# 2_MCU_schdoc.net
KiCad netlist of a schematic drawn in Altium Designer
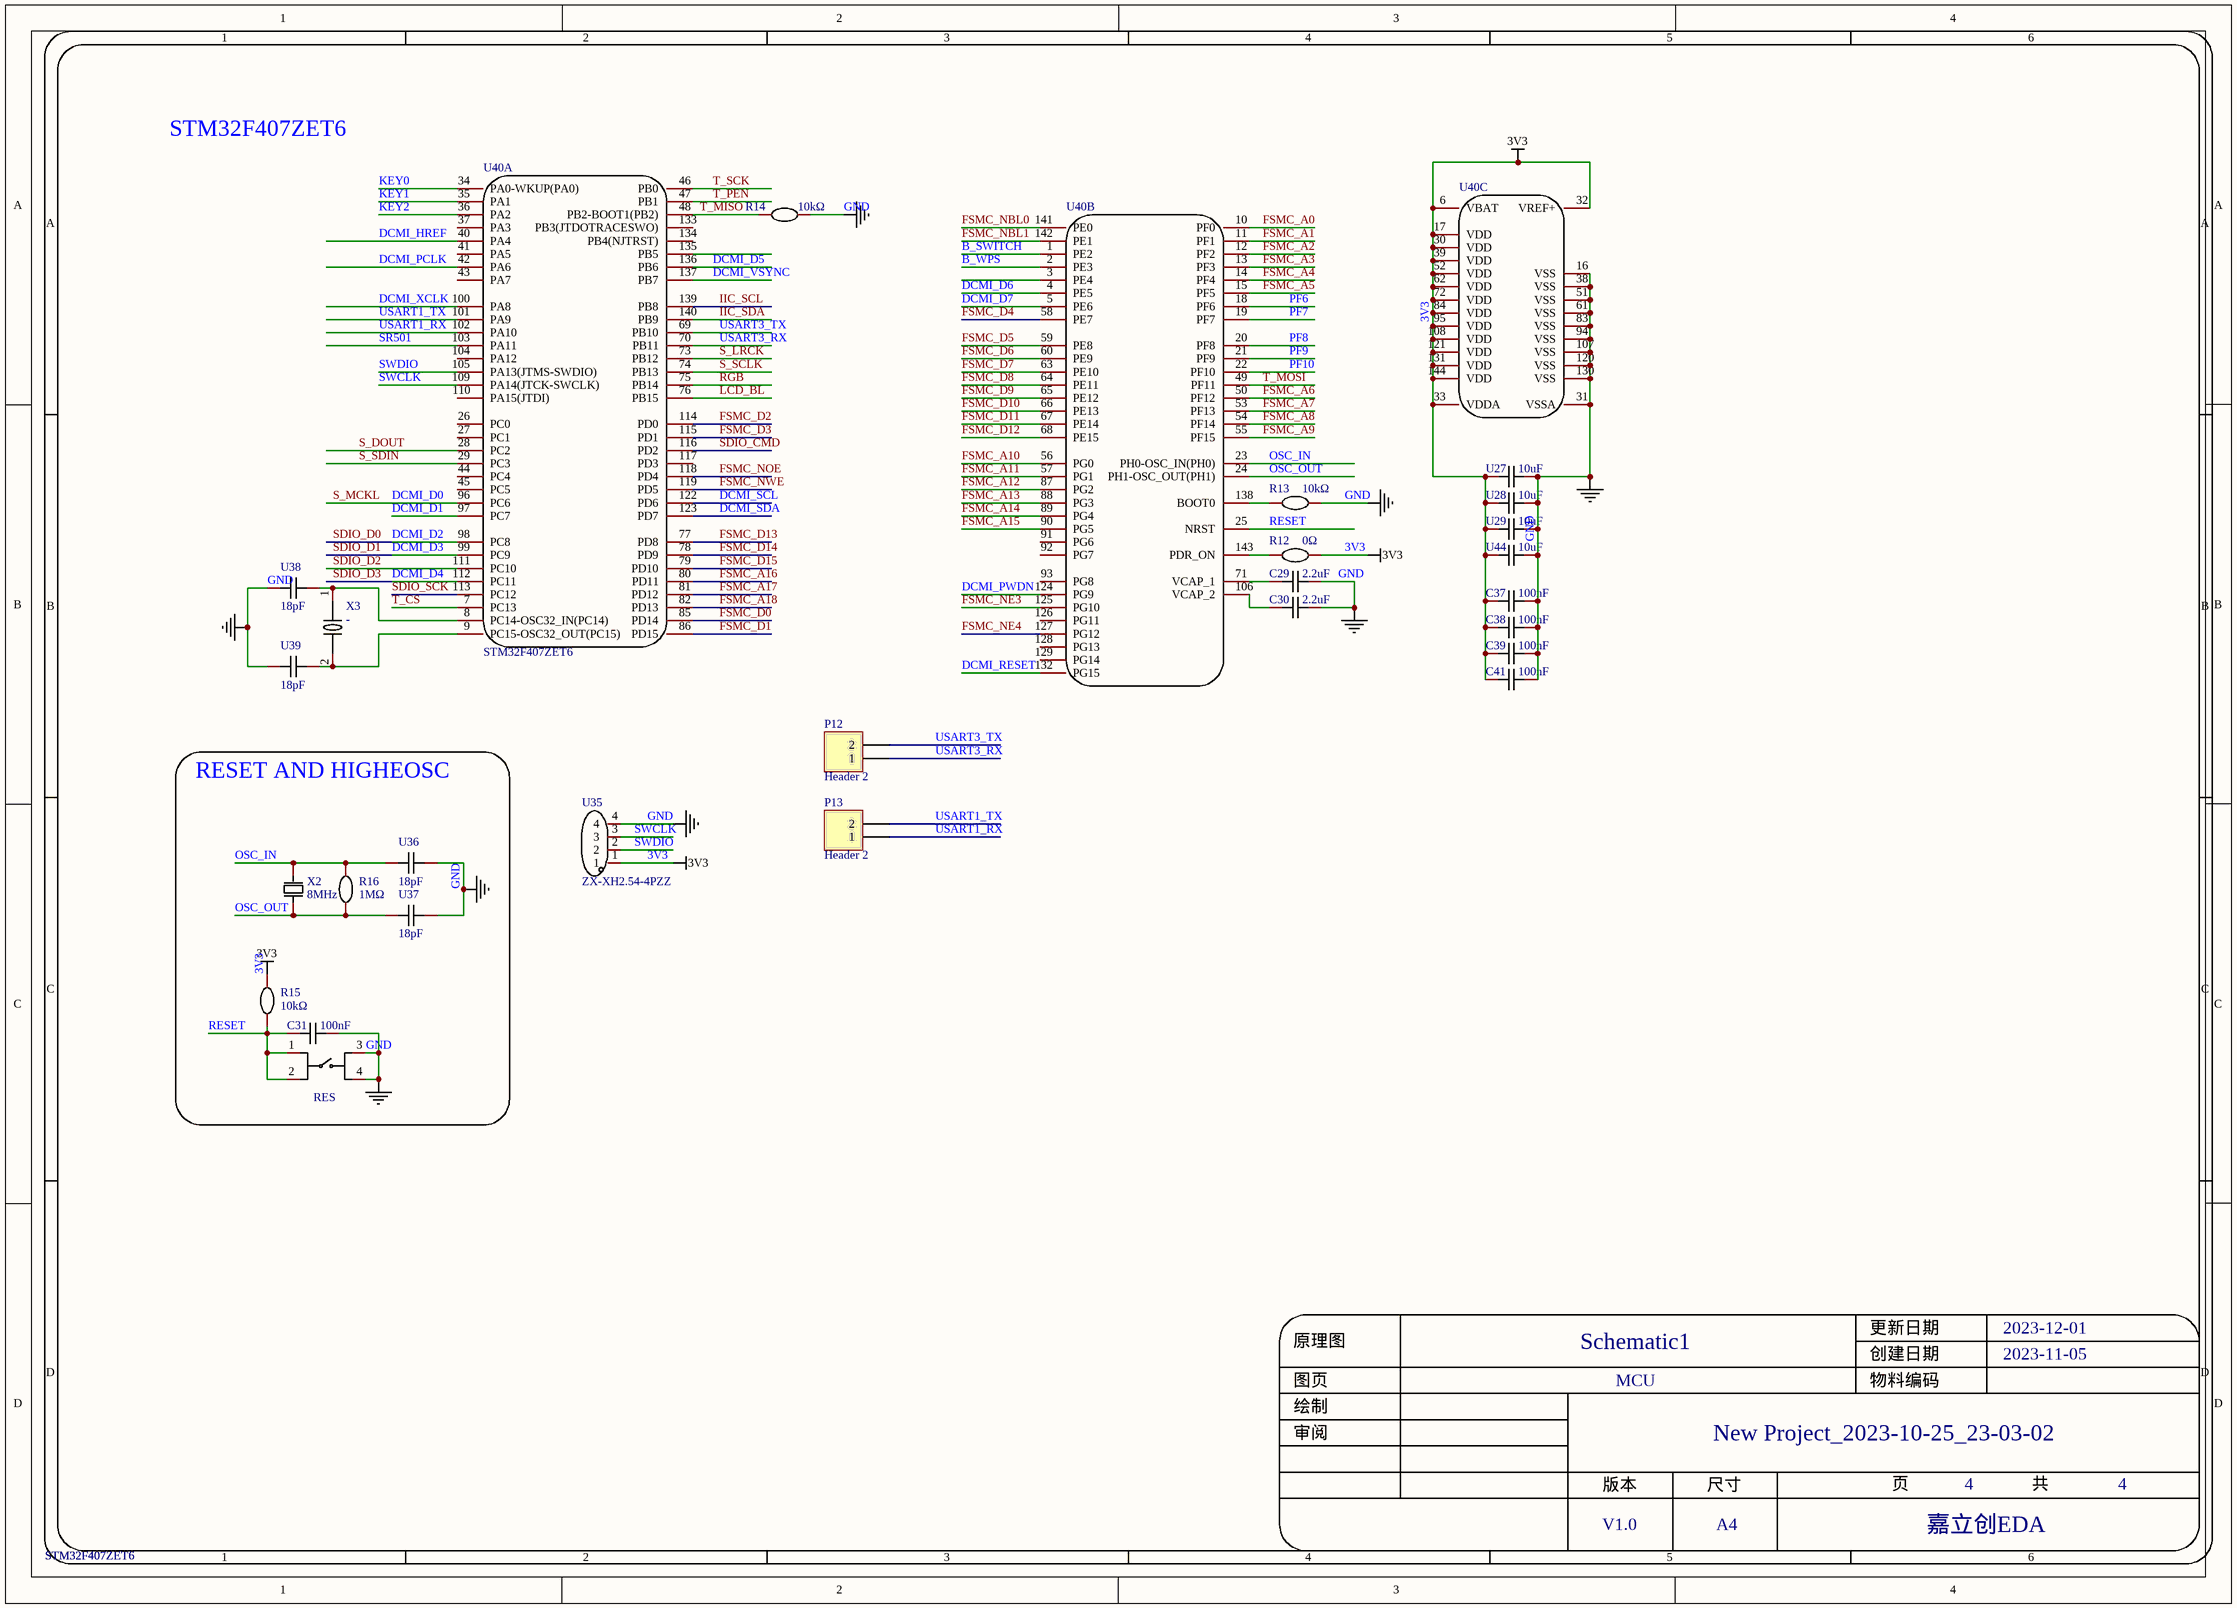
[diagram p0: 2_MCU.schdoc.schdoc]

(export (version "E")
  (design (tool "Eeschema 10.0.6"))
  (components
    (comp (ref "C29")
      (value "2.2uF")
      (footprint "C0603")
      (description "容值:2.2uF;精度:±10%;额定电压:10V;材质(温度系数):X6S;")
      (fields
        (field (name "NAME") "2.2uF")
        (field (name "MANUFACTURER") "TDK")
        (field (name "MANUFACTURER PART") "C1608X6S1A225K080AB")
      )
      (libsource (lib "altium-import") (part "root_0_C1608X6S1A225K080AB_"))
    )
    (comp (ref "C30")
      (value "2.2uF")
      (footprint "C0603")
      (description "容值:2.2uF;精度:±10%;额定电压:10V;材质(温度系数):X6S;")
      (fields
        (field (name "NAME") "2.2uF")
        (field (name "MANUFACTURER") "TDK")
        (field (name "MANUFACTURER PART") "C1608X6S1A225K080AB")
      )
      (libsource (lib "altium-import") (part "root_0_C1608X6S1A225K080AB_"))
    )
    (comp (ref "C31")
      (value "100nF")
      (footprint "C0603")
      (description "容值:100nF;精度:±20%;额定电压:50V;材质(温度系数):X8R;")
      (fields
        (field (name "NAME") "100nF")
        (field (name "MANUFACTURER") "TDK")
        (field (name "MANUFACTURER PART") "CGA3E3X8R1H104M080AE")
      )
      (libsource (lib "altium-import") (part "root_0_CGA3E3X8R1H104M080AE_"))
    )
    (comp (ref "C37")
      (value "100nF")
      (footprint "C0603")
      (description "容值:100nF;精度:±20%;额定电压:50V;材质(温度系数):X8R;")
      (fields
        (field (name "NAME") "100nF")
        (field (name "MANUFACTURER") "TDK")
        (field (name "MANUFACTURER PART") "CGA3E3X8R1H104M080AE")
      )
      (libsource (lib "altium-import") (part "root_0_CGA3E3X8R1H104M080AE_"))
    )
    (comp (ref "C38")
      (value "100nF")
      (footprint "C0603")
      (description "容值:100nF;精度:±20%;额定电压:50V;材质(温度系数):X8R;")
      (fields
        (field (name "NAME") "100nF")
        (field (name "MANUFACTURER") "TDK")
        (field (name "MANUFACTURER PART") "CGA3E3X8R1H104M080AE")
      )
      (libsource (lib "altium-import") (part "root_0_CGA3E3X8R1H104M080AE_"))
    )
    (comp (ref "C39")
      (value "100nF")
      (footprint "C0603")
      (description "容值:100nF;精度:±20%;额定电压:50V;材质(温度系数):X8R;")
      (fields
        (field (name "NAME") "100nF")
        (field (name "MANUFACTURER") "TDK")
        (field (name "MANUFACTURER PART") "CGA3E3X8R1H104M080AE")
      )
      (libsource (lib "altium-import") (part "root_0_CGA3E3X8R1H104M080AE_"))
    )
    (comp (ref "C41")
      (value "100nF")
      (footprint "C0603")
      (description "容值:100nF;精度:±20%;额定电压:50V;材质(温度系数):X8R;")
      (fields
        (field (name "NAME") "100nF")
        (field (name "MANUFACTURER") "TDK")
        (field (name "MANUFACTURER PART") "CGA3E3X8R1H104M080AE")
      )
      (libsource (lib "altium-import") (part "root_0_CGA3E3X8R1H104M080AE_"))
    )
    (comp (ref "P12")
      (value "Header 2")
      (footprint "HDR1X2")
      (description "Header, 2-Pin")
      (fields (field (name "PUBLISHER") "Altium Limited"))
      (libsource (lib "Miscellaneous Connectors") (part "Header 2"))
    )
    (comp (ref "P13")
      (value "Header 2")
      (footprint "HDR1X2")
      (description "Header, 2-Pin")
      (fields (field (name "PUBLISHER") "Altium Limited"))
      (libsource (lib "Miscellaneous Connectors") (part "Header 2"))
    )
    (comp (ref "R12")
      (value "0Ω")
      (footprint "R0603")
      (description "电阻类型:厚膜电阻;阻值:0Ω;精度:-;功率:100mW;")
      (fields
        (field (name "NAME") "0Ω")
        (field (name "MANUFACTURER") "YAGEO(国巨)")
        (field (name "MANUFACTURER PART") "RC0603JR-130RL")
      )
      (libsource (lib "altium-import") (part "root_0_RC0603JR-130RL_"))
    )
    (comp (ref "R13")
      (value "10kΩ")
      (footprint "R0603")
      (description "阻值:10kΩ;精度:±5%;")
      (fields
        (field (name "NAME") "10kΩ")
        (field (name "MANUFACTURER") "VO(翔胜)")
        (field (name "MANUFACTURER PART") "SCR0603J10K")
      )
      (libsource (lib "altium-import") (part "root_0_SCR0603J10K_"))
    )
    (comp (ref "R14")
      (value "10kΩ")
      (footprint "R0603")
      (description "阻值:10kΩ;精度:±5%;")
      (fields
        (field (name "NAME") "10kΩ")
        (field (name "MANUFACTURER") "VO(翔胜)")
        (field (name "MANUFACTURER PART") "SCR0603J10K")
      )
      (libsource (lib "altium-import") (part "root_0_SCR0603J10K_"))
    )
    (comp (ref "R15")
      (value "10kΩ")
      (footprint "R0603")
      (description "阻值:10kΩ;精度:±5%;")
      (fields
        (field (name "NAME") "10kΩ")
        (field (name "MANUFACTURER") "VO(翔胜)")
        (field (name "MANUFACTURER PART") "SCR0603J10K")
      )
      (libsource (lib "altium-import") (part "root_1_SCR0603J10K_"))
    )
    (comp (ref "R16")
      (value "1MΩ")
      (footprint "R0603")
      (description "电阻类型:厚膜电阻;阻值:1MΩ;精度:±5%;功率:100mW;")
      (fields
        (field (name "NAME") "1MΩ")
        (field (name "MANUFACTURER") "VISHAY(威世)")
        (field (name "MANUFACTURER PART") "CRCW06031M00JNEAC")
      )
      (libsource (lib "altium-import") (part "root_1_CRCW06031M00JNEAC_"))
    )
    (comp (ref "RES")
      (value "K2-6639SP-C4SC-04")
      (footprint "KEY-SMD_4P-L6.0-W6.0-P3.90-LS10.0")
      (fields (field (name "MANUFACTURER") "韩国韩荣"))
      (libsource (lib "altium-import") (part "root_0_K2-6639SP-C4SC-04_"))
    )
    (comp (ref "U27")
      (value "10uF")
      (footprint "C0603")
      (description "容值:10uF;精度:±20%;额定电压:16V;材质(温度系数):JB;")
      (fields
        (field (name "NAME") "10uF")
        (field (name "MANUFACTURER") "TDK")
        (field (name "MANUFACTURER PART") "C1608JB1C106M080AB")
      )
      (libsource (lib "altium-import") (part "root_0_C1608JB1C106M080AB_"))
    )
    (comp (ref "U28")
      (value "10uF")
      (footprint "C0603")
      (description "容值:10uF;精度:±20%;额定电压:16V;材质(温度系数):JB;")
      (fields
        (field (name "NAME") "10uF")
        (field (name "MANUFACTURER") "TDK")
        (field (name "MANUFACTURER PART") "C1608JB1C106M080AB")
      )
      (libsource (lib "altium-import") (part "root_0_C1608JB1C106M080AB_"))
    )
    (comp (ref "U29")
      (value "10uF")
      (footprint "C0603")
      (description "容值:10uF;精度:±20%;额定电压:16V;材质(温度系数):JB;")
      (fields
        (field (name "NAME") "10uF")
        (field (name "MANUFACTURER") "TDK")
        (field (name "MANUFACTURER PART") "C1608JB1C106M080AB")
      )
      (libsource (lib "altium-import") (part "root_0_C1608JB1C106M080AB_"))
    )
    (comp (ref "U35")
      (value "ZX-XH2.54-4PZZ")
      (footprint "CONN-TH_4P-P2.50_4PIN")
      (fields (field (name "NAME") "ZX-XH2.54-4PZZ") (field (name "MANUFACTURER") "Megastar(兆星)"))
      (libsource (lib "altium-import") (part "root_2_ZX-XH2.54-4PZZ_"))
    )
    (comp (ref "U36")
      (value "18pF")
      (footprint "C0603")
      (description "容值:18pF;精度:±5%;额定电压:100V;材质(温度系数):CH;")
      (fields
        (field (name "NAME") "18pF")
        (field (name "MANUFACTURER") "TDK")
        (field (name "MANUFACTURER PART") "C1608CH2A180J080AA")
      )
      (libsource (lib "altium-import") (part "root_0_C1608CH2A180J080AA_"))
    )
    (comp (ref "U37")
      (value "18pF")
      (footprint "C0603")
      (description "容值:18pF;精度:±5%;额定电压:100V;材质(温度系数):CH;")
      (fields
        (field (name "NAME") "18pF")
        (field (name "MANUFACTURER") "TDK")
        (field (name "MANUFACTURER PART") "C1608CH2A180J080AA")
      )
      (libsource (lib "altium-import") (part "root_0_C1608CH2A180J080AA_"))
    )
    (comp (ref "U38")
      (value "18pF")
      (footprint "C0603")
      (description "容值:18pF;精度:±5%;额定电压:100V;材质(温度系数):CH;")
      (fields
        (field (name "NAME") "18pF")
        (field (name "MANUFACTURER") "TDK")
        (field (name "MANUFACTURER PART") "C1608CH2A180J080AA")
      )
      (libsource (lib "altium-import") (part "root_0_C1608CH2A180J080AA_"))
    )
    (comp (ref "U39")
      (value "18pF")
      (footprint "C0603")
      (description "容值:18pF;精度:±5%;额定电压:100V;材质(温度系数):CH;")
      (fields
        (field (name "NAME") "18pF")
        (field (name "MANUFACTURER") "TDK")
        (field (name "MANUFACTURER PART") "C1608CH2A180J080AA")
      )
      (libsource (lib "altium-import") (part "root_0_C1608CH2A180J080AA_"))
    )
    (comp (ref "U40")
      (value "STM32F407ZET6")
      (footprint "LQFP-144_L20.0-W20.0-P0.50-LS22.0-BL")
      (fields (field (name "NAME") "STM32F407ZET6") (field (name "MANUFACTURER") "ST(意法半导体)"))
      (libsource (lib "altium-import") (part "root_0_STM32F407ZET6_"))
    )
    (comp (ref "U44")
      (value "10uF")
      (footprint "C0603")
      (description "容值:10uF;精度:±20%;额定电压:16V;材质(温度系数):JB;")
      (fields
        (field (name "NAME") "10uF")
        (field (name "MANUFACTURER") "TDK")
        (field (name "MANUFACTURER PART") "C1608JB1C106M080AB")
      )
      (libsource (lib "altium-import") (part "root_0_C1608JB1C106M080AB_"))
    )
    (comp (ref "X2")
      (value "8MHz")
      (footprint "OSC-SMD_L5.0-W3.2")
      (description "频率:8MHz;频率公差:±30ppm;负载电容:20pF;")
      (fields
        (field (name "NAME") "8MHz")
        (field (name "MANUFACTURER") "TAE(雅晶鑫)")
        (field (name "MANUFACTURER PART") "TAXM8M2QLFCDT1T")
      )
      (libsource (lib "altium-import") (part "root_1_TAXM8M2QLFCDT1T_"))
    )
    (comp (ref "X3")
      (value "-")
      (footprint "OSC-SMD_2P-L1.6-W1.0")
      (description "频率:-;负载电容:-;")
      (fields
        (field (name "NAME") "-")
        (field (name "MANUFACTURER") "RIVER(大河)")
        (field (name "MANUFACTURER PART") "TFX-04-32.768K")
      )
      (libsource (lib "altium-import") (part "root_3_TFX-04-32.768K_"))
    )
  )
  (nets
    (net (code "1") (name "/B_SWITCH") (class "Default")
      (node (ref "U40") (pin "1") (pinfunction "PE2_1") (pintype "passive"))
    )
    (net (code "2") (name "/B_WPS") (class "Default")
      (node (ref "U40") (pin "2") (pinfunction "PE3_2") (pintype "passive"))
    )
    (net (code "3") (name "/DCMI_D0") (class "Default")
      (node (ref "U40") (pin "96") (pinfunction "PC6_96") (pintype "passive"))
    )
    (net (code "4") (name "/DCMI_D1") (class "Default")
      (node (ref "U40") (pin "97") (pinfunction "PC7_97") (pintype "passive"))
    )
    (net (code "5") (name "/DCMI_D2") (class "Default")
      (node (ref "U40") (pin "98") (pinfunction "PC8_98") (pintype "passive"))
    )
    (net (code "6") (name "/DCMI_D3") (class "Default")
      (node (ref "U40") (pin "99") (pinfunction "PC9_99") (pintype "passive"))
    )
    (net (code "7") (name "/DCMI_D4") (class "Default")
      (node (ref "U40") (pin "112") (pinfunction "PC11_112") (pintype "passive"))
    )
    (net (code "8") (name "/DCMI_D5") (class "Default")
      (node (ref "U40") (pin "136") (pinfunction "PB6_136") (pintype "passive"))
    )
    (net (code "9") (name "/DCMI_D6") (class "Default")
      (node (ref "U40") (pin "4") (pinfunction "PE5_4") (pintype "passive"))
    )
    (net (code "10") (name "/DCMI_D7") (class "Default")
      (node (ref "U40") (pin "5") (pinfunction "PE6_5") (pintype "passive"))
    )
    (net (code "11") (name "/DCMI_HREF") (class "Default")
      (node (ref "U40") (pin "40") (pinfunction "PA4_40") (pintype "passive"))
    )
    (net (code "12") (name "/DCMI_PCLK") (class "Default")
      (node (ref "U40") (pin "42") (pinfunction "PA6_42") (pintype "passive"))
    )
    (net (code "13") (name "/DCMI_PWDN") (class "Default")
      (node (ref "U40") (pin "124") (pinfunction "PG9_124") (pintype "passive"))
    )
    (net (code "14") (name "/DCMI_RESET") (class "Default")
      (node (ref "U40") (pin "132") (pinfunction "PG15_132") (pintype "passive"))
    )
    (net (code "15") (name "/DCMI_SCL") (class "Default")
      (node (ref "U40") (pin "122") (pinfunction "PD6_122") (pintype "passive"))
    )
    (net (code "16") (name "/DCMI_SDA") (class "Default")
      (node (ref "U40") (pin "123") (pinfunction "PD7_123") (pintype "passive"))
    )
    (net (code "17") (name "/DCMI_VSYNC") (class "Default")
      (node (ref "U40") (pin "137") (pinfunction "PB7_137") (pintype "passive"))
    )
    (net (code "18") (name "/DCMI_XCLK") (class "Default")
      (node (ref "U40") (pin "100") (pinfunction "PA8_100") (pintype "passive"))
    )
    (net (code "19") (name "/FSMC_A0") (class "Default")
      (node (ref "U40") (pin "10") (pinfunction "PF0_10") (pintype "passive"))
    )
    (net (code "20") (name "/FSMC_A1") (class "Default")
      (node (ref "U40") (pin "11") (pinfunction "PF1_11") (pintype "passive"))
    )
    (net (code "21") (name "/FSMC_A2") (class "Default")
      (node (ref "U40") (pin "12") (pinfunction "PF2_12") (pintype "passive"))
    )
    (net (code "22") (name "/FSMC_A3") (class "Default")
      (node (ref "U40") (pin "13") (pinfunction "PF3_13") (pintype "passive"))
    )
    (net (code "23") (name "/FSMC_A4") (class "Default")
      (node (ref "U40") (pin "14") (pinfunction "PF4_14") (pintype "passive"))
    )
    (net (code "24") (name "/FSMC_A5") (class "Default")
      (node (ref "U40") (pin "15") (pinfunction "PF5_15") (pintype "passive"))
    )
    (net (code "25") (name "/FSMC_A6") (class "Default")
      (node (ref "U40") (pin "50") (pinfunction "PF12_50") (pintype "passive"))
    )
    (net (code "26") (name "/FSMC_A7") (class "Default")
      (node (ref "U40") (pin "53") (pinfunction "PF13_53") (pintype "passive"))
    )
    (net (code "27") (name "/FSMC_A8") (class "Default")
      (node (ref "U40") (pin "54") (pinfunction "PF14_54") (pintype "passive"))
    )
    (net (code "28") (name "/FSMC_A9") (class "Default")
      (node (ref "U40") (pin "55") (pinfunction "PF15_55") (pintype "passive"))
    )
    (net (code "29") (name "/FSMC_A10") (class "Default")
      (node (ref "U40") (pin "56") (pinfunction "PG0_56") (pintype "passive"))
    )
    (net (code "30") (name "/FSMC_A11") (class "Default")
      (node (ref "U40") (pin "57") (pinfunction "PG1_57") (pintype "passive"))
    )
    (net (code "31") (name "/FSMC_A12") (class "Default")
      (node (ref "U40") (pin "87") (pinfunction "PG2_87") (pintype "passive"))
    )
    (net (code "32") (name "/FSMC_A13") (class "Default")
      (node (ref "U40") (pin "88") (pinfunction "PG3_88") (pintype "passive"))
    )
    (net (code "33") (name "/FSMC_A14") (class "Default")
      (node (ref "U40") (pin "89") (pinfunction "PG4_89") (pintype "passive"))
    )
    (net (code "34") (name "/FSMC_A15") (class "Default")
      (node (ref "U40") (pin "90") (pinfunction "PG5_90") (pintype "passive"))
    )
    (net (code "35") (name "/FSMC_A16") (class "Default")
      (node (ref "U40") (pin "80") (pinfunction "PD11_80") (pintype "passive"))
    )
    (net (code "36") (name "/FSMC_A17") (class "Default")
      (node (ref "U40") (pin "81") (pinfunction "PD12_81") (pintype "passive"))
    )
    (net (code "37") (name "/FSMC_A18") (class "Default")
      (node (ref "U40") (pin "82") (pinfunction "PD13_82") (pintype "passive"))
    )
    (net (code "38") (name "/FSMC_D0") (class "Default")
      (node (ref "U40") (pin "85") (pinfunction "PD14_85") (pintype "passive"))
    )
    (net (code "39") (name "/FSMC_D1") (class "Default")
      (node (ref "U40") (pin "86") (pinfunction "PD15_86") (pintype "passive"))
    )
    (net (code "40") (name "/FSMC_D2") (class "Default")
      (node (ref "U40") (pin "114") (pinfunction "PD0_114") (pintype "passive"))
    )
    (net (code "41") (name "/FSMC_D3") (class "Default")
      (node (ref "U40") (pin "115") (pinfunction "PD1_115") (pintype "passive"))
    )
    (net (code "42") (name "/FSMC_D4") (class "Default")
      (node (ref "U40") (pin "58") (pinfunction "PE7_58") (pintype "passive"))
    )
    (net (code "43") (name "/FSMC_D5") (class "Default")
      (node (ref "U40") (pin "59") (pinfunction "PE8_59") (pintype "passive"))
    )
    (net (code "44") (name "/FSMC_D6") (class "Default")
      (node (ref "U40") (pin "60") (pinfunction "PE9_60") (pintype "passive"))
    )
    (net (code "45") (name "/FSMC_D7") (class "Default")
      (node (ref "U40") (pin "63") (pinfunction "PE10_63") (pintype "passive"))
    )
    (net (code "46") (name "/FSMC_D8") (class "Default")
      (node (ref "U40") (pin "64") (pinfunction "PE11_64") (pintype "passive"))
    )
    (net (code "47") (name "/FSMC_D9") (class "Default")
      (node (ref "U40") (pin "65") (pinfunction "PE12_65") (pintype "passive"))
    )
    (net (code "48") (name "/FSMC_D10") (class "Default")
      (node (ref "U40") (pin "66") (pinfunction "PE13_66") (pintype "passive"))
    )
    (net (code "49") (name "/FSMC_D11") (class "Default")
      (node (ref "U40") (pin "67") (pinfunction "PE14_67") (pintype "passive"))
    )
    (net (code "50") (name "/FSMC_D12") (class "Default")
      (node (ref "U40") (pin "68") (pinfunction "PE15_68") (pintype "passive"))
    )
    (net (code "51") (name "/FSMC_D13") (class "Default")
      (node (ref "U40") (pin "77") (pinfunction "PD8_77") (pintype "passive"))
    )
    (net (code "52") (name "/FSMC_D14") (class "Default")
      (node (ref "U40") (pin "78") (pinfunction "PD9_78") (pintype "passive"))
    )
    (net (code "53") (name "/FSMC_D15") (class "Default")
      (node (ref "U40") (pin "79") (pinfunction "PD10_79") (pintype "passive"))
    )
    (net (code "54") (name "/FSMC_NBL0") (class "Default")
      (node (ref "U40") (pin "141") (pinfunction "PE0_141") (pintype "passive"))
    )
    (net (code "55") (name "/FSMC_NBL1") (class "Default")
      (node (ref "U40") (pin "142") (pinfunction "PE1_142") (pintype "passive"))
    )
    (net (code "56") (name "/FSMC_NE3") (class "Default")
      (node (ref "U40") (pin "125") (pinfunction "PG10_125") (pintype "passive"))
    )
    (net (code "57") (name "/FSMC_NE4") (class "Default")
      (node (ref "U40") (pin "127") (pinfunction "PG12_127") (pintype "passive"))
    )
    (net (code "58") (name "/FSMC_NOE") (class "Default")
      (node (ref "U40") (pin "118") (pinfunction "PD4_118") (pintype "passive"))
    )
    (net (code "59") (name "/FSMC_NWE") (class "Default")
      (node (ref "U40") (pin "119") (pinfunction "PD5_119") (pintype "passive"))
    )
    (net (code "60") (name "/GND") (class "Default")
      (node (ref "C29") (pin "2") (pinfunction "2_2") (pintype "passive"))
      (node (ref "C30") (pin "2") (pinfunction "2_2") (pintype "passive"))
      (node (ref "C31") (pin "2") (pinfunction "2_2") (pintype "passive"))
      (node (ref "C37") (pin "2") (pinfunction "2_2") (pintype "passive"))
      (node (ref "C38") (pin "2") (pinfunction "2_2") (pintype "passive"))
      (node (ref "C39") (pin "2") (pinfunction "2_2") (pintype "passive"))
      (node (ref "C41") (pin "2") (pinfunction "2_2") (pintype "passive"))
      (node (ref "R13") (pin "2") (pinfunction "2_2") (pintype "passive"))
      (node (ref "R14") (pin "2") (pinfunction "2_2") (pintype "passive"))
      (node (ref "RES") (pin "3") (pinfunction "3_3") (pintype "passive"))
      (node (ref "RES") (pin "4") (pinfunction "4_4") (pintype "passive"))
      (node (ref "U27") (pin "2") (pinfunction "2_2") (pintype "passive"))
      (node (ref "U28") (pin "2") (pinfunction "2_2") (pintype "passive"))
      (node (ref "U29") (pin "2") (pinfunction "2_2") (pintype "passive"))
      (node (ref "U35") (pin "4") (pinfunction "4_4") (pintype "passive"))
      (node (ref "U36") (pin "2") (pinfunction "2_2") (pintype "passive"))
      (node (ref "U37") (pin "2") (pinfunction "2_2") (pintype "passive"))
      (node (ref "U38") (pin "1") (pinfunction "1_1") (pintype "passive"))
      (node (ref "U39") (pin "1") (pinfunction "1_1") (pintype "passive"))
      (node (ref "U40") (pin "107") (pinfunction "VSS_107") (pintype "passive"))
      (node (ref "U40") (pin "120") (pinfunction "VSS_120") (pintype "passive"))
      (node (ref "U40") (pin "130") (pinfunction "VSS_130") (pintype "passive"))
      (node (ref "U40") (pin "16") (pinfunction "VSS_16") (pintype "passive"))
      (node (ref "U40") (pin "31") (pinfunction "VSSA_31") (pintype "passive"))
      (node (ref "U40") (pin "38") (pinfunction "VSS_38") (pintype "passive"))
      (node (ref "U40") (pin "51") (pinfunction "VSS_51") (pintype "passive"))
      (node (ref "U40") (pin "61") (pinfunction "VSS_61") (pintype "passive"))
      (node (ref "U40") (pin "83") (pinfunction "VSS_83") (pintype "passive"))
      (node (ref "U40") (pin "94") (pinfunction "VSS_94") (pintype "passive"))
      (node (ref "U44") (pin "2") (pinfunction "2_2") (pintype "passive"))
    )
    (net (code "61") (name "/IIC_SCL") (class "Default")
      (node (ref "U40") (pin "139") (pinfunction "PB8_139") (pintype "passive"))
    )
    (net (code "62") (name "/IIC_SDA") (class "Default")
      (node (ref "U40") (pin "140") (pinfunction "PB9_140") (pintype "passive"))
    )
    (net (code "63") (name "/KEY0") (class "Default")
      (node (ref "U40") (pin "34") (pinfunction "PA0-WKUP(PA0)_34") (pintype "passive"))
    )
    (net (code "64") (name "/KEY1") (class "Default")
      (node (ref "U40") (pin "35") (pinfunction "PA1_35") (pintype "passive"))
    )
    (net (code "65") (name "/KEY2") (class "Default")
      (node (ref "U40") (pin "36") (pinfunction "PA2_36") (pintype "passive"))
    )
    (net (code "66") (name "/LCD_BL") (class "Default")
      (node (ref "U40") (pin "76") (pinfunction "PB15_76") (pintype "passive"))
    )
    (net (code "67") (name "/OSC_IN") (class "Default")
      (node (ref "R16") (pin "2") (pinfunction "2_2") (pintype "passive"))
      (node (ref "U36") (pin "1") (pinfunction "1_1") (pintype "passive"))
      (node (ref "U40") (pin "23") (pinfunction "PH0-OSC_IN(PH0)_23") (pintype "passive"))
      (node (ref "X2") (pin "2") (pinfunction "OSC2_2") (pintype "passive"))
    )
    (net (code "68") (name "/OSC_OUT") (class "Default")
      (node (ref "R16") (pin "1") (pinfunction "1_1") (pintype "passive"))
      (node (ref "U37") (pin "1") (pinfunction "1_1") (pintype "passive"))
      (node (ref "U40") (pin "24") (pinfunction "PH1-OSC_OUT(PH1)_24") (pintype "passive"))
      (node (ref "X2") (pin "1") (pinfunction "OSC1_1") (pintype "passive"))
    )
    (net (code "69") (name "/PF6") (class "Default")
      (node (ref "U40") (pin "18") (pinfunction "PF6_18") (pintype "passive"))
    )
    (net (code "70") (name "/PF7") (class "Default")
      (node (ref "U40") (pin "19") (pinfunction "PF7_19") (pintype "passive"))
    )
    (net (code "71") (name "/PF8") (class "Default")
      (node (ref "U40") (pin "20") (pinfunction "PF8_20") (pintype "passive"))
    )
    (net (code "72") (name "/PF9") (class "Default")
      (node (ref "U40") (pin "21") (pinfunction "PF9_21") (pintype "passive"))
    )
    (net (code "73") (name "/PF10") (class "Default")
      (node (ref "U40") (pin "22") (pinfunction "PF10_22") (pintype "passive"))
    )
    (net (code "74") (name "/RESET") (class "Default")
      (node (ref "C31") (pin "1") (pinfunction "1_1") (pintype "passive"))
      (node (ref "R15") (pin "1") (pinfunction "1_1") (pintype "passive"))
      (node (ref "RES") (pin "1") (pinfunction "1_1") (pintype "passive"))
      (node (ref "RES") (pin "2") (pinfunction "2_2") (pintype "passive"))
      (node (ref "U40") (pin "25") (pinfunction "NRST_25") (pintype "passive"))
    )
    (net (code "75") (name "/RGB") (class "Default")
      (node (ref "U40") (pin "75") (pinfunction "PB14_75") (pintype "passive"))
    )
    (net (code "76") (name "/SDIO_CMD") (class "Default")
      (node (ref "U40") (pin "116") (pinfunction "PD2_116") (pintype "passive"))
    )
    (net (code "77") (name "/SDIO_D2") (class "Default")
      (node (ref "U40") (pin "111") (pinfunction "PC10_111") (pintype "passive"))
    )
    (net (code "78") (name "/SDIO_SCK") (class "Default")
      (node (ref "U40") (pin "113") (pinfunction "PC12_113") (pintype "passive"))
    )
    (net (code "79") (name "/SR501") (class "Default")
      (node (ref "U40") (pin "103") (pinfunction "PA11_103") (pintype "passive"))
    )
    (net (code "80") (name "/SWCLK") (class "Default")
      (node (ref "U35") (pin "3") (pinfunction "3_3") (pintype "passive"))
      (node (ref "U40") (pin "109") (pinfunction "PA14(JTCK-SWCLK)_109") (pintype "passive"))
    )
    (net (code "81") (name "/SWDIO") (class "Default")
      (node (ref "U35") (pin "2") (pinfunction "2_2") (pintype "passive"))
      (node (ref "U40") (pin "105") (pinfunction "PA13(JTMS-SWDIO)_105") (pintype "passive"))
    )
    (net (code "82") (name "/S_DOUT") (class "Default")
      (node (ref "U40") (pin "28") (pinfunction "PC2_28") (pintype "passive"))
    )
    (net (code "83") (name "/S_LRCK") (class "Default")
      (node (ref "U40") (pin "73") (pinfunction "PB12_73") (pintype "passive"))
    )
    (net (code "84") (name "/S_SCLK") (class "Default")
      (node (ref "U40") (pin "74") (pinfunction "PB13_74") (pintype "passive"))
    )
    (net (code "85") (name "/S_SDIN") (class "Default")
      (node (ref "U40") (pin "29") (pinfunction "PC3_29") (pintype "passive"))
    )
    (net (code "86") (name "/T_CS") (class "Default")
      (node (ref "U40") (pin "7") (pinfunction "PC13_7") (pintype "passive"))
    )
    (net (code "87") (name "/T_MISO") (class "Default")
      (node (ref "R14") (pin "1") (pinfunction "1_1") (pintype "passive"))
      (node (ref "U40") (pin "48") (pinfunction "PB2-BOOT1(PB2)_48") (pintype "passive"))
    )
    (net (code "88") (name "/T_MOSI") (class "Default")
      (node (ref "U40") (pin "49") (pinfunction "PF11_49") (pintype "passive"))
    )
    (net (code "89") (name "/T_PEN") (class "Default")
      (node (ref "U40") (pin "47") (pinfunction "PB1_47") (pintype "passive"))
    )
    (net (code "90") (name "/T_SCK") (class "Default")
      (node (ref "U40") (pin "46") (pinfunction "PB0_46") (pintype "passive"))
    )
    (net (code "91") (name "/USART1_RX") (class "Default")
      (node (ref "P13") (pin "1") (pinfunction "1_1") (pintype "passive"))
      (node (ref "U40") (pin "102") (pinfunction "PA10_102") (pintype "passive"))
    )
    (net (code "92") (name "/USART1_TX") (class "Default")
      (node (ref "P13") (pin "2") (pinfunction "2_2") (pintype "passive"))
      (node (ref "U40") (pin "101") (pinfunction "PA9_101") (pintype "passive"))
    )
    (net (code "93") (name "/USART3_RX") (class "Default")
      (node (ref "P12") (pin "1") (pinfunction "1_1") (pintype "passive"))
      (node (ref "U40") (pin "70") (pinfunction "PB11_70") (pintype "passive"))
    )
    (net (code "94") (name "/USART3_TX") (class "Default")
      (node (ref "P12") (pin "2") (pinfunction "2_2") (pintype "passive"))
      (node (ref "U40") (pin "69") (pinfunction "PB10_69") (pintype "passive"))
    )
    (net (code "95") (name "3V3") (class "Default")
      (node (ref "C37") (pin "1") (pinfunction "1_1") (pintype "passive"))
      (node (ref "C38") (pin "1") (pinfunction "1_1") (pintype "passive"))
      (node (ref "C39") (pin "1") (pinfunction "1_1") (pintype "passive"))
      (node (ref "C41") (pin "1") (pinfunction "1_1") (pintype "passive"))
      (node (ref "R12") (pin "2") (pinfunction "2_2") (pintype "passive"))
      (node (ref "R15") (pin "2") (pinfunction "2_2") (pintype "passive"))
      (node (ref "U27") (pin "1") (pinfunction "1_1") (pintype "passive"))
      (node (ref "U28") (pin "1") (pinfunction "1_1") (pintype "passive"))
      (node (ref "U29") (pin "1") (pinfunction "1_1") (pintype "passive"))
      (node (ref "U35") (pin "1") (pinfunction "1_1") (pintype "passive"))
      (node (ref "U40") (pin "108") (pinfunction "VDD_108") (pintype "passive"))
      (node (ref "U40") (pin "121") (pinfunction "VDD_121") (pintype "passive"))
      (node (ref "U40") (pin "131") (pinfunction "VDD_131") (pintype "passive"))
      (node (ref "U40") (pin "144") (pinfunction "VDD_144") (pintype "passive"))
      (node (ref "U40") (pin "17") (pinfunction "VDD_17") (pintype "passive"))
      (node (ref "U40") (pin "30") (pinfunction "VDD_30") (pintype "passive"))
      (node (ref "U40") (pin "32") (pinfunction "VREF+_32") (pintype "passive"))
      (node (ref "U40") (pin "33") (pinfunction "VDDA_33") (pintype "passive"))
      (node (ref "U40") (pin "39") (pinfunction "VDD_39") (pintype "passive"))
      (node (ref "U40") (pin "52") (pinfunction "VDD_52") (pintype "passive"))
      (node (ref "U40") (pin "6") (pinfunction "VBAT_6") (pintype "passive"))
      (node (ref "U40") (pin "62") (pinfunction "VDD_62") (pintype "passive"))
      (node (ref "U40") (pin "72") (pinfunction "VDD_72") (pintype "passive"))
      (node (ref "U40") (pin "84") (pinfunction "VDD_84") (pintype "passive"))
      (node (ref "U40") (pin "95") (pinfunction "VDD_95") (pintype "passive"))
      (node (ref "U44") (pin "1") (pinfunction "1_1") (pintype "passive"))
    )
    (net (code "96") (name "Net-(U40A-PC14-OSC32_IN(PC14))") (class "Default")
      (node (ref "U38") (pin "2") (pinfunction "2_2") (pintype "passive"))
      (node (ref "U40") (pin "8") (pinfunction "PC14-OSC32_IN(PC14)_8") (pintype "passive"))
      (node (ref "X3") (pin "1") (pinfunction "1_1") (pintype "passive"))
    )
    (net (code "97") (name "Net-(U40A-PC15-OSC32_OUT(PC15))") (class "Default")
      (node (ref "U39") (pin "2") (pinfunction "2_2") (pintype "passive"))
      (node (ref "U40") (pin "9") (pinfunction "PC15-OSC32_OUT(PC15)_9") (pintype "passive"))
      (node (ref "X3") (pin "2") (pinfunction "2_2") (pintype "passive"))
    )
    (net (code "98") (name "Net-(U40B-BOOT0)") (class "Default")
      (node (ref "R13") (pin "1") (pinfunction "1_1") (pintype "passive"))
      (node (ref "U40") (pin "138") (pinfunction "BOOT0_138") (pintype "passive"))
    )
    (net (code "99") (name "Net-(U40B-PDR_ON)") (class "Default")
      (node (ref "R12") (pin "1") (pinfunction "1_1") (pintype "passive"))
      (node (ref "U40") (pin "143") (pinfunction "PDR_ON_143") (pintype "passive"))
    )
    (net (code "100") (name "Net-(U40B-VCAP_1)") (class "Default")
      (node (ref "C29") (pin "1") (pinfunction "1_1") (pintype "passive"))
      (node (ref "U40") (pin "71") (pinfunction "VCAP_1_71") (pintype "passive"))
    )
    (net (code "101") (name "Net-(U40B-VCAP_2)") (class "Default")
      (node (ref "C30") (pin "1") (pinfunction "1_1") (pintype "passive"))
      (node (ref "U40") (pin "106") (pinfunction "VCAP_2_106") (pintype "passive"))
    )
    (net (code "102") (name "unconnected-(U40A-PA3-Pad37)") (class "Default")
      (node (ref "U40") (pin "37") (pinfunction "PA3_37") (pintype "passive"))
    )
    (net (code "103") (name "unconnected-(U40A-PA5-Pad41)") (class "Default")
      (node (ref "U40") (pin "41") (pinfunction "PA5_41") (pintype "passive"))
    )
    (net (code "104") (name "unconnected-(U40A-PA7-Pad43)") (class "Default")
      (node (ref "U40") (pin "43") (pinfunction "PA7_43") (pintype "passive"))
    )
    (net (code "105") (name "unconnected-(U40A-PA12-Pad104)") (class "Default")
      (node (ref "U40") (pin "104") (pinfunction "PA12_104") (pintype "passive"))
    )
    (net (code "106") (name "unconnected-(U40A-PA15(JTDI)-Pad110)") (class "Default")
      (node (ref "U40") (pin "110") (pinfunction "PA15(JTDI)_110") (pintype "passive"))
    )
    (net (code "107") (name "unconnected-(U40A-PB3(JTDOTRACESWO)-Pad133)") (class "Default")
      (node (ref "U40") (pin "133") (pinfunction "PB3(JTDOTRACESWO)_133") (pintype "passive"))
    )
    (net (code "108") (name "unconnected-(U40A-PB4(NJTRST)-Pad134)") (class "Default")
      (node (ref "U40") (pin "134") (pinfunction "PB4(NJTRST)_134") (pintype "passive"))
    )
    (net (code "109") (name "unconnected-(U40A-PB5-Pad135)") (class "Default")
      (node (ref "U40") (pin "135") (pinfunction "PB5_135") (pintype "passive"))
    )
    (net (code "110") (name "unconnected-(U40A-PC0-Pad26)") (class "Default")
      (node (ref "U40") (pin "26") (pinfunction "PC0_26") (pintype "passive"))
    )
    (net (code "111") (name "unconnected-(U40A-PC1-Pad27)") (class "Default")
      (node (ref "U40") (pin "27") (pinfunction "PC1_27") (pintype "passive"))
    )
    (net (code "112") (name "unconnected-(U40A-PC4-Pad44)") (class "Default")
      (node (ref "U40") (pin "44") (pinfunction "PC4_44") (pintype "passive"))
    )
    (net (code "113") (name "unconnected-(U40A-PC5-Pad45)") (class "Default")
      (node (ref "U40") (pin "45") (pinfunction "PC5_45") (pintype "passive"))
    )
    (net (code "114") (name "unconnected-(U40A-PD3-Pad117)") (class "Default")
      (node (ref "U40") (pin "117") (pinfunction "PD3_117") (pintype "passive"))
    )
    (net (code "115") (name "unconnected-(U40B-PE4-Pad3)") (class "Default")
      (node (ref "U40") (pin "3") (pinfunction "PE4_3") (pintype "passive"))
    )
    (net (code "116") (name "unconnected-(U40B-PG6-Pad91)") (class "Default")
      (node (ref "U40") (pin "91") (pinfunction "PG6_91") (pintype "passive"))
    )
    (net (code "117") (name "unconnected-(U40B-PG7-Pad92)") (class "Default")
      (node (ref "U40") (pin "92") (pinfunction "PG7_92") (pintype "passive"))
    )
    (net (code "118") (name "unconnected-(U40B-PG8-Pad93)") (class "Default")
      (node (ref "U40") (pin "93") (pinfunction "PG8_93") (pintype "passive"))
    )
    (net (code "119") (name "unconnected-(U40B-PG11-Pad126)") (class "Default")
      (node (ref "U40") (pin "126") (pinfunction "PG11_126") (pintype "passive"))
    )
    (net (code "120") (name "unconnected-(U40B-PG13-Pad128)") (class "Default")
      (node (ref "U40") (pin "128") (pinfunction "PG13_128") (pintype "passive"))
    )
    (net (code "121") (name "unconnected-(U40B-PG14-Pad129)") (class "Default")
      (node (ref "U40") (pin "129") (pinfunction "PG14_129") (pintype "passive"))
    )
  )
)
